# EPIP_v173.net
KiCad netlist of a schematic drawn in EAGLE
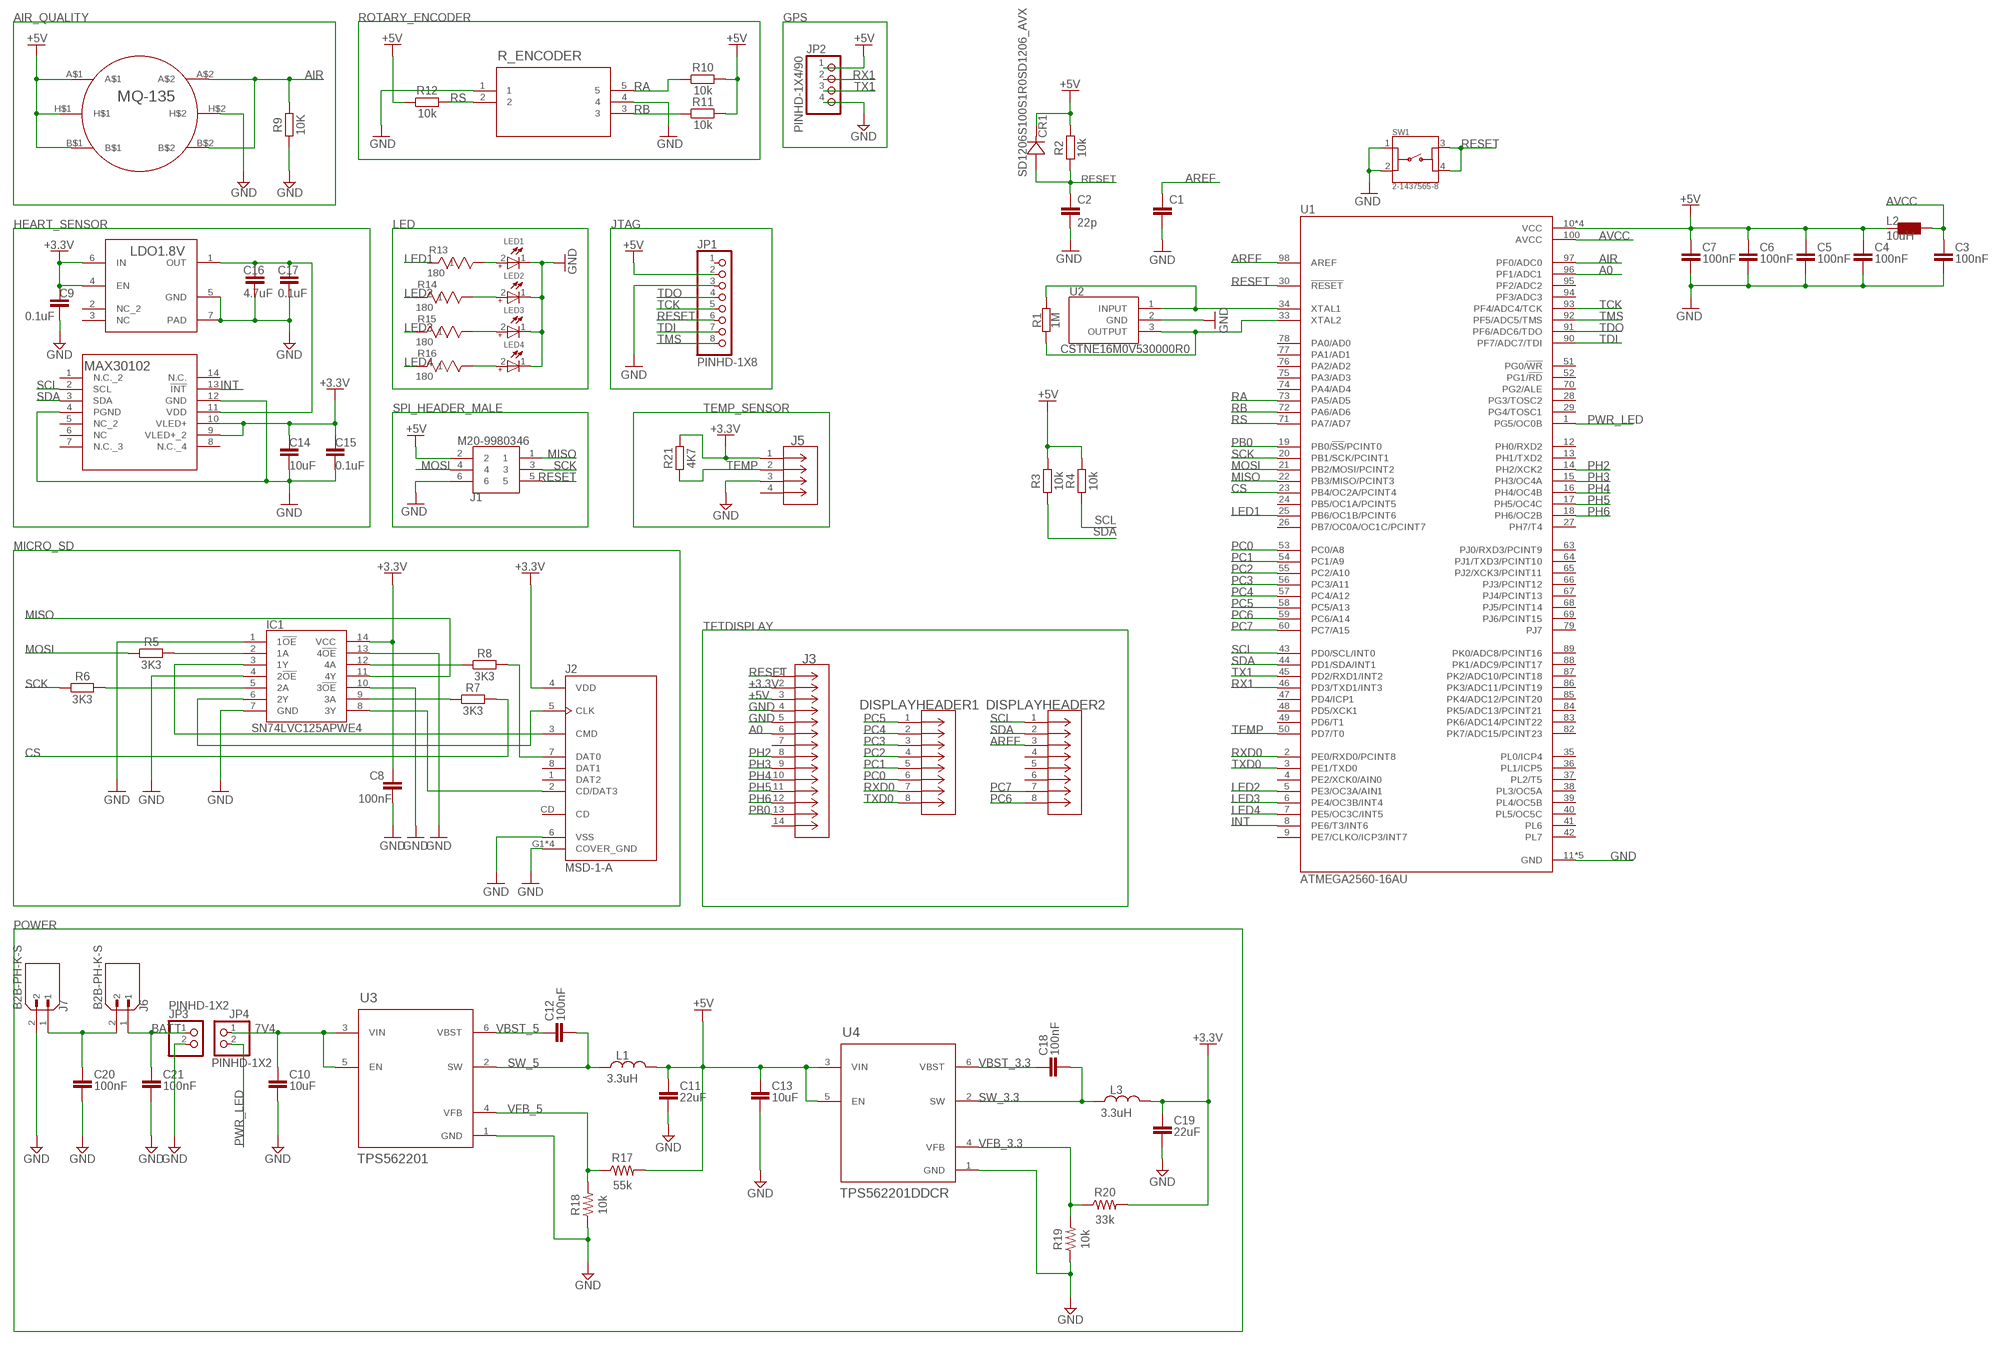
[diagram p0: schematic, sheet 1]

(export (version "E")
  (design (tool "Eeschema 10.0.6"))
  (components
    (comp (ref "C1")
      (value "100nF")
      (footprint "eagle-import:CAPC1608X85")
      (libsource (lib "eagle-import") (part "CCHIP-0603(1608-METRIC)_"))
    )
    (comp (ref "C2")
      (value "22p")
      (footprint "eagle-import:C0603-ROUND")
      (fields (field (name "PART_NUMBER") "22pF_0603"))
      (libsource (lib "eagle-import") (part "0014_22PF_0603"))
    )
    (comp (ref "C3")
      (value "100nF")
      (footprint "eagle-import:CAPC1608X85")
      (libsource (lib "eagle-import") (part "CCHIP-0603(1608-METRIC)_"))
    )
    (comp (ref "C4")
      (value "100nF")
      (footprint "eagle-import:CAPC1608X85")
      (libsource (lib "eagle-import") (part "CCHIP-0603(1608-METRIC)_"))
    )
    (comp (ref "C5")
      (value "100nF")
      (footprint "eagle-import:CAPC1608X85")
      (libsource (lib "eagle-import") (part "CCHIP-0603(1608-METRIC)_"))
    )
    (comp (ref "C6")
      (value "100nF")
      (footprint "eagle-import:CAPC1608X85")
      (libsource (lib "eagle-import") (part "CCHIP-0603(1608-METRIC)_"))
    )
    (comp (ref "C7")
      (value "100nF")
      (footprint "eagle-import:CAPC1608X85")
      (libsource (lib "eagle-import") (part "CCHIP-0603(1608-METRIC)_"))
    )
    (comp (ref "C8")
      (value "100nF")
      (footprint "eagle-import:CAPC1608X85")
      (libsource (lib "eagle-import") (part "CCHIP-0603(1608-METRIC)_"))
    )
    (comp (ref "C9")
      (value "0.1uF")
      (footprint "eagle-import:CAPC2012X110")
      (libsource (lib "eagle-import") (part "CCHIP-0805(2012-METRIC)_"))
    )
    (comp (ref "C10")
      (value "10uF")
      (footprint "eagle-import:CAPC2012X110")
      (libsource (lib "eagle-import") (part "CCHIP-0805(2012-METRIC)_"))
    )
    (comp (ref "C11")
      (value "22uF")
      (footprint "eagle-import:CAPC2012X110")
      (libsource (lib "eagle-import") (part "CCHIP-0805(2012-METRIC)_"))
    )
    (comp (ref "C12")
      (value "100nF")
      (footprint "eagle-import:CAPC1608X85")
      (libsource (lib "eagle-import") (part "CCHIP-0603(1608-METRIC)_"))
    )
    (comp (ref "C13")
      (value "10uF")
      (footprint "eagle-import:CAPC2012X110")
      (libsource (lib "eagle-import") (part "CCHIP-0805(2012-METRIC)_"))
    )
    (comp (ref "C14")
      (value "10uF")
      (footprint "eagle-import:CAPC2012X110")
      (libsource (lib "eagle-import") (part "CCHIP-0805(2012-METRIC)_"))
    )
    (comp (ref "C15")
      (value "0.1uF")
      (footprint "eagle-import:CAPC2012X110")
      (libsource (lib "eagle-import") (part "CCHIP-0805(2012-METRIC)_"))
    )
    (comp (ref "C16")
      (value "4.7uF")
      (footprint "eagle-import:CAPC1608X85")
      (libsource (lib "eagle-import") (part "CCHIP-0603(1608-METRIC)_"))
    )
    (comp (ref "C17")
      (value "0.1uF")
      (footprint "eagle-import:CAPC2012X110")
      (libsource (lib "eagle-import") (part "CCHIP-0805(2012-METRIC)_"))
    )
    (comp (ref "C18")
      (value "100nF")
      (footprint "eagle-import:CAPC1608X85")
      (libsource (lib "eagle-import") (part "CCHIP-0603(1608-METRIC)_"))
    )
    (comp (ref "C19")
      (value "22uF")
      (footprint "eagle-import:CAPC2012X110")
      (libsource (lib "eagle-import") (part "CCHIP-0805(2012-METRIC)_"))
    )
    (comp (ref "C20")
      (value "100nF")
      (footprint "eagle-import:CAPC1608X85")
      (libsource (lib "eagle-import") (part "CCHIP-0603(1608-METRIC)_"))
    )
    (comp (ref "C21")
      (value "100nF")
      (footprint "eagle-import:CAPC1608X85")
      (libsource (lib "eagle-import") (part "CCHIP-0603(1608-METRIC)_"))
    )
    (comp (ref "CR1")
      (value "SD1206S100S1R0SD1206_AVX")
      (footprint "eagle-import:SD1206_AVX")
      (fields
        (field (name "MANUFACTURER_PART_NUMBER") "SD1206S100S1R0")
        (field (name "COPYRIGHT") "Copyright (C) 2024 Ultra Librarian. All rights reserved.")
      )
      (libsource (lib "eagle-import") (part "SD1206S100S1R0SD1206_AVX"))
    )
    (comp (ref "DISPLAYHEADER1")
      (value "PPPC081LFBN-RCCONN8_LFBN-RC_SUL")
      (footprint "eagle-import:CONN8_LFBN-RC_SUL")
      (fields
        (field (name "MANUFACTURER_PART_NUMBER") "PPPC081LFBN-RC")
        (field (name "COPYRIGHT") "Copyright (C) 2024 Ultra Librarian. All rights reserved.")
      )
      (libsource (lib "eagle-import") (part "PPPC081LFBN-RCCONN8_LFBN-RC_SUL"))
    )
    (comp (ref "DISPLAYHEADER2")
      (value "PPPC081LFBN-RCCONN8_LFBN-RC_SUL")
      (footprint "eagle-import:CONN8_LFBN-RC_SUL")
      (fields
        (field (name "MANUFACTURER_PART_NUMBER") "PPPC081LFBN-RC")
        (field (name "COPYRIGHT") "Copyright (C) 2024 Ultra Librarian. All rights reserved.")
      )
      (libsource (lib "eagle-import") (part "PPPC081LFBN-RCCONN8_LFBN-RC_SUL"))
    )
    (comp (ref "IC1")
      (value "SN74LVC125APWE4")
      (footprint "eagle-import:SOP65P640X120-14N")
      (fields (field (name "MOUSER_PART_NUMBER") "595-SN74LVC125APWE4"))
      (libsource (lib "eagle-import") (part "SN74LVC125APWE4"))
    )
    (comp (ref "J1")
      (value "M20-9980346")
      (footprint "eagle-import:HDRV6W64P254_2X3_762X508X868P")
      (fields (field (name "MOUSER_PART_NUMBER") "855-M20-9980346"))
      (libsource (lib "eagle-import") (part "M20-9980346"))
    )
    (comp (ref "J2")
      (value "MSD-1-A")
      (footprint "eagle-import:CUI_MSD-1-A")
      (fields (field (name "MANUFACTURER") "CUI Devices"))
      (libsource (lib "eagle-import") (part "MSD-1-A"))
    )
    (comp (ref "J3")
      (value "PPPC141LFBN-RCCONN14_PPPN141_SUL")
      (footprint "eagle-import:CONN14_PPPN141_SUL")
      (fields
        (field (name "MANUFACTURER_PART_NUMBER") "PPPC141LFBN-RC")
        (field (name "COPYRIGHT") "Copyright (C) 2024 Ultra Librarian. All rights reserved.")
      )
      (libsource (lib "eagle-import") (part "PPPC141LFBN-RCCONN14_PPPN141_SUL"))
    )
    (comp (ref "J5")
      (value "PPTC041LFBN-RCCONN_PPTC041LFBN-RC_SUL")
      (footprint "eagle-import:CONN_PPTC041LFBN-RC_SUL")
      (fields
        (field (name "MANUFACTURER_PART_NUMBER") "PPTC041LFBN-RC")
        (field (name "COPYRIGHT") "Copyright (C) 2024 Ultra Librarian. All rights reserved.")
      )
      (libsource (lib "eagle-import") (part "PPTC041LFBN-RCCONN_PPTC041LFBN-RC_SUL"))
    )
    (comp (ref "J6")
      (value "B2B-PH-K-S")
      (footprint "eagle-import:JST_B2B-PH-K-S")
      (fields (field (name "MANUFACTURER") "JST"))
      (libsource (lib "eagle-import") (part "B2B-PH-K-S"))
    )
    (comp (ref "J7")
      (value "B2B-PH-K-S")
      (footprint "eagle-import:JST_B2B-PH-K-S")
      (fields (field (name "MANUFACTURER") "JST"))
      (libsource (lib "eagle-import") (part "B2B-PH-K-S"))
    )
    (comp (ref "JP1")
      (value "PINHD-1X8")
      (footprint "eagle-import:1X08")
      (fields (field (name "MANUFACTURER") "Generic"))
      (libsource (lib "eagle-import") (part "PINHD-1X8"))
    )
    (comp (ref "JP2")
      (value "PINHD-1X4/90")
      (footprint "eagle-import:1X04_90")
      (fields (field (name "MANUFACTURER") "Generic"))
      (libsource (lib "eagle-import") (part "PINHD-1X4/90"))
    )
    (comp (ref "JP3")
      (value "PINHD-1X2")
      (footprint "eagle-import:1X02")
      (fields (field (name "MANUFACTURER") "Generic"))
      (libsource (lib "eagle-import") (part "PINHD-1X2"))
    )
    (comp (ref "JP4")
      (value "PINHD-1X2")
      (footprint "eagle-import:1X02")
      (fields (field (name "MANUFACTURER") "Generic"))
      (libsource (lib "eagle-import") (part "PINHD-1X2"))
    )
    (comp (ref "L1")
      (value "3.3uH")
      (footprint "eagle-import:INDC2520X120N")
      (libsource (lib "eagle-import") (part "LCHIP-1008(2520-METRIC)_"))
    )
    (comp (ref "L2")
      (value "10uH")
      (footprint "eagle-import:0805")
      (fields (field (name "PART_NUMBER") "CV201210-100K"))
      (libsource (lib "eagle-import") (part "0715_CV201210-100K"))
    )
    (comp (ref "L3")
      (value "3.3uH")
      (footprint "eagle-import:INDC2520X120N")
      (libsource (lib "eagle-import") (part "LCHIP-1008(2520-METRIC)_"))
    )
    (comp (ref "LDO1.8V")
      (value "LP5910-1.8DRVRDRV0006A_NV")
      (footprint "eagle-import:DRV0006A_NV")
      (fields
        (field (name "MANUFACTURER_PART_NUMBER") "LP5910-1.8DRVR")
        (field (name "COPYRIGHT") "Copyright (C) 2024 Ultra Librarian. All rights reserved.")
      )
      (libsource (lib "eagle-import") (part "LP5910-1.8DRVRDRV0006A_NV"))
    )
    (comp (ref "LED1")
      (value "WL-TMRW_3MM_WITHOUTSTOPPER")
      (footprint "eagle-import:WL-TMRW_3MM")
      (libsource (lib "eagle-import") (part "WL-TMRW_3MM_WITHOUTSTOPPER"))
    )
    (comp (ref "LED2")
      (value "WL-TMRW_3MM_WITHOUTSTOPPER")
      (footprint "eagle-import:WL-TMRW_3MM")
      (libsource (lib "eagle-import") (part "WL-TMRW_3MM_WITHOUTSTOPPER"))
    )
    (comp (ref "LED3")
      (value "WL-TMRW_3MM_WITHOUTSTOPPER")
      (footprint "eagle-import:WL-TMRW_3MM")
      (libsource (lib "eagle-import") (part "WL-TMRW_3MM_WITHOUTSTOPPER"))
    )
    (comp (ref "LED4")
      (value "WL-TMRW_3MM_WITHOUTSTOPPER")
      (footprint "eagle-import:WL-TMRW_3MM")
      (libsource (lib "eagle-import") (part "WL-TMRW_3MM_WITHOUTSTOPPER"))
    )
    (comp (ref "MAX30102")
      (value "MAX30102EFD+T21-1048_F143A5+1_MXM-L")
      (footprint "eagle-import:21-1048_F143A5+1_MXM-L")
      (fields
        (field (name "MANUFACTURER_PART_NUMBER") "MAX30102EFD+T")
        (field (name "COPYRIGHT") "Copyright (C) 2024 Ultra Librarian. All rights reserved.")
      )
      (libsource (lib "eagle-import") (part "MAX30102EFD+T21-1048_F143A5+1_MXM-L"))
    )
    (comp (ref "R1")
      (value "1M")
      (footprint "eagle-import:RESC1608X60")
      (libsource (lib "eagle-import") (part "RCHIP-0603(1608-METRIC)_"))
    )
    (comp (ref "R2")
      (value "10k")
      (footprint "eagle-import:RESC2012X65")
      (libsource (lib "eagle-import") (part "RCHIP-0805(2012-METRIC)_"))
    )
    (comp (ref "R3")
      (value "10k")
      (footprint "eagle-import:RESC2012X65")
      (libsource (lib "eagle-import") (part "RCHIP-0805(2012-METRIC)_"))
    )
    (comp (ref "R4")
      (value "10k")
      (footprint "eagle-import:RESC2012X65")
      (libsource (lib "eagle-import") (part "RCHIP-0805(2012-METRIC)_"))
    )
    (comp (ref "R5")
      (value "3K3")
      (footprint "eagle-import:RESC2012X65")
      (libsource (lib "eagle-import") (part "RCHIP-0805(2012-METRIC)_"))
    )
    (comp (ref "R6")
      (value "3K3")
      (footprint "eagle-import:RESC2012X65")
      (libsource (lib "eagle-import") (part "RCHIP-0805(2012-METRIC)_"))
    )
    (comp (ref "R7")
      (value "3K3")
      (footprint "eagle-import:RESC2012X65")
      (libsource (lib "eagle-import") (part "RCHIP-0805(2012-METRIC)_"))
    )
    (comp (ref "R8")
      (value "3K3")
      (footprint "eagle-import:RESC2012X65")
      (libsource (lib "eagle-import") (part "RCHIP-0805(2012-METRIC)_"))
    )
    (comp (ref "R9")
      (value "10K")
      (footprint "eagle-import:RESC2012X65")
      (libsource (lib "eagle-import") (part "RESISTOR_CHIP-0805(2012-METRIC)_"))
    )
    (comp (ref "R10")
      (value "10k")
      (footprint "eagle-import:RESC2012X65")
      (libsource (lib "eagle-import") (part "RCHIP-0805(2012-METRIC)_"))
    )
    (comp (ref "R11")
      (value "10k")
      (footprint "eagle-import:RESC2012X65")
      (libsource (lib "eagle-import") (part "RCHIP-0805(2012-METRIC)_"))
    )
    (comp (ref "R12")
      (value "10k")
      (footprint "eagle-import:RESC2012X65")
      (libsource (lib "eagle-import") (part "RCHIP-0805(2012-METRIC)_"))
    )
    (comp (ref "R13")
      (value "180")
      (footprint "eagle-import:STA_RMCF0805_STP-L")
      (fields
        (field (name "MANUFACTURER_PART_NUMBER") "RMCF0805JT180R")
        (field (name "COPYRIGHT") "Copyright (C) 2024 Ultra Librarian. All rights reserved.")
      )
      (libsource (lib "eagle-import") (part "RMCF0805JT180RSTA_RMCF0805_STP-L"))
    )
    (comp (ref "R14")
      (value "180")
      (footprint "eagle-import:STA_RMCF0805_STP-L")
      (fields
        (field (name "MANUFACTURER_PART_NUMBER") "RMCF0805JT180R")
        (field (name "COPYRIGHT") "Copyright (C) 2024 Ultra Librarian. All rights reserved.")
      )
      (libsource (lib "eagle-import") (part "RMCF0805JT180RSTA_RMCF0805_STP-L"))
    )
    (comp (ref "R15")
      (value "180")
      (footprint "eagle-import:STA_RMCF0805_STP-L")
      (fields
        (field (name "MANUFACTURER_PART_NUMBER") "RMCF0805JT180R")
        (field (name "COPYRIGHT") "Copyright (C) 2024 Ultra Librarian. All rights reserved.")
      )
      (libsource (lib "eagle-import") (part "RMCF0805JT180RSTA_RMCF0805_STP-L"))
    )
    (comp (ref "R16")
      (value "180")
      (footprint "eagle-import:STA_RMCF0805_STP-L")
      (fields
        (field (name "MANUFACTURER_PART_NUMBER") "RMCF0805JT180R")
        (field (name "COPYRIGHT") "Copyright (C) 2024 Ultra Librarian. All rights reserved.")
      )
      (libsource (lib "eagle-import") (part "RMCF0805JT180RSTA_RMCF0805_STP-L"))
    )
    (comp (ref "R17")
      (value "55k")
      (footprint "eagle-import:RESC2012X65")
      (libsource (lib "eagle-import") (part "R-USCHIP-0805(2012-METRIC)_"))
    )
    (comp (ref "R18")
      (value "10k")
      (footprint "eagle-import:RESC2012X65")
      (libsource (lib "eagle-import") (part "R-USCHIP-0805(2012-METRIC)_"))
    )
    (comp (ref "R19")
      (value "10k")
      (footprint "eagle-import:RESC2012X65")
      (libsource (lib "eagle-import") (part "R-USCHIP-0805(2012-METRIC)_"))
    )
    (comp (ref "R20")
      (value "33k")
      (footprint "eagle-import:RESC2012X65")
      (libsource (lib "eagle-import") (part "R-USCHIP-0805(2012-METRIC)_"))
    )
    (comp (ref "R21")
      (value "4K7")
      (footprint "eagle-import:RESC2012X65")
      (libsource (lib "eagle-import") (part "RCHIP-0805(2012-METRIC)_"))
    )
    (comp (ref "R_ENCODER")
      (value "EN12-HS22AF30EN12")
      (footprint "eagle-import:EN12-HS_TTE")
      (fields
        (field (name "MANUFACTURER_PART_NUMBER") "EN12-HS22AF30")
        (field (name "COPYRIGHT") "Copyright (C) 2024 Ultra Librarian. All rights reserved.")
      )
      (libsource (lib "eagle-import") (part "EN12-HS22AF30EN12-HS_TTE"))
    )
    (comp (ref "SW1")
      (value "2-1437565-8")
      (footprint "eagle-import:SW_SMD_2-1437565-8_4_4.50_6.00_6.00_5.00")
      (fields (field (name "MANUFACTURER") "TE connectivity"))
      (libsource (lib "eagle-import") (part "2-1437565-8"))
    )
    (comp (ref "U$2")
      (value "MQ_135_A")
      (footprint "eagle-import:MQ-135")
      (libsource (lib "eagle-import") (part "MQ_135_A"))
    )
    (comp (ref "U1")
      (value "ATMEGA2560-16AU")
      (footprint "eagle-import:QFP50P1600X1600X120-100N")
      (fields (field (name "MANUFACTURER") "Microchip Technology"))
      (libsource (lib "eagle-import") (part "ATMEGA2560-16AU"))
    )
    (comp (ref "U2")
      (value "CSTNE16M0V530000R0")
      (footprint "eagle-import:CSTNE16M0V530000R0")
      (fields (field (name "MOUSER_PART_NUMBER") "81-CSTNE16M0V530000R"))
      (libsource (lib "eagle-import") (part "CSTNE16M0V530000R0"))
    )
    (comp (ref "U3")
      (value "TPS562201")
      (footprint "eagle-import:DDC0006A_L")
      (fields
        (field (name "MANUFACTURER_PART_NUMBER") "TPS562201DDCR")
        (field (name "COPYRIGHT") "Copyright (C) 2024 Ultra Librarian. All rights reserved.")
      )
      (libsource (lib "eagle-import") (part "TPS562201DDCRDDC0006A_L"))
    )
    (comp (ref "U4")
      (value "TPS562201DDCR")
      (footprint "eagle-import:DDC0006A_L")
      (fields (field (name "COPYRIGHT") "Copyright (C) 2024 Ultra Librarian. All rights reserved."))
      (libsource (lib "eagle-import") (part "TPS562201DDCRDDC0006A_L"))
    )
  )
  (nets
    (net (code "1") (name "+3.3V") (class "Default")
      (node (ref "C14") (pin "1") (pinfunction "1_1") (pintype "passive"))
      (node (ref "C15") (pin "1") (pinfunction "1_1") (pintype "passive"))
      (node (ref "C19") (pin "1") (pinfunction "1_1") (pintype "passive"))
      (node (ref "C8") (pin "1") (pinfunction "1_1") (pintype "passive"))
      (node (ref "C9") (pin "1") (pinfunction "1_1") (pintype "passive"))
      (node (ref "IC1") (pin "14") (pinfunction "VCC_14") (pintype "bidirectional"))
      (node (ref "J2") (pin "4") (pinfunction "VDD_4") (pintype "power_in"))
      (node (ref "J3") (pin "2") (pinfunction "2_2") (pintype "passive"))
      (node (ref "J5") (pin "1") (pinfunction "1_1") (pintype "passive"))
      (node (ref "L3") (pin "2") (pinfunction "2_2") (pintype "passive"))
      (node (ref "LDO1.8V") (pin "4") (pinfunction "EN_4") (pintype "input"))
      (node (ref "LDO1.8V") (pin "6") (pinfunction "IN_6") (pintype "power_in"))
      (node (ref "MAX30102") (pin "10") (pinfunction "VLED+_10") (pintype "passive"))
      (node (ref "MAX30102") (pin "9") (pinfunction "VLED+_2_9") (pintype "passive"))
      (node (ref "R20") (pin "2") (pinfunction "2_2") (pintype "passive"))
      (node (ref "R21") (pin "2") (pinfunction "2_2") (pintype "passive"))
    )
    (net (code "2") (name "+5V") (class "Default")
      (node (ref "C11") (pin "1") (pinfunction "1_1") (pintype "passive"))
      (node (ref "C13") (pin "1") (pinfunction "1_1") (pintype "passive"))
      (node (ref "C4") (pin "1") (pinfunction "1_1") (pintype "passive"))
      (node (ref "C5") (pin "1") (pinfunction "1_1") (pintype "passive"))
      (node (ref "C6") (pin "1") (pinfunction "1_1") (pintype "passive"))
      (node (ref "C7") (pin "1") (pinfunction "1_1") (pintype "passive"))
      (node (ref "CR1") (pin "1") (pinfunction "1_1") (pintype "passive"))
      (node (ref "J1") (pin "2") (pinfunction "2_2") (pintype "bidirectional"))
      (node (ref "J3") (pin "3") (pinfunction "3_3") (pintype "passive"))
      (node (ref "JP1") (pin "2") (pinfunction "2_2") (pintype "passive"))
      (node (ref "JP2") (pin "1") (pinfunction "1_1") (pintype "passive"))
      (node (ref "L1") (pin "2") (pinfunction "2_2") (pintype "passive"))
      (node (ref "L2") (pin "2") (pinfunction "2_2") (pintype "passive"))
      (node (ref "R10") (pin "2") (pinfunction "2_2") (pintype "passive"))
      (node (ref "R11") (pin "2") (pinfunction "2_2") (pintype "passive"))
      (node (ref "R12") (pin "1") (pinfunction "1_1") (pintype "passive"))
      (node (ref "R17") (pin "2") (pinfunction "2_2") (pintype "passive"))
      (node (ref "R2") (pin "2") (pinfunction "2_2") (pintype "passive"))
      (node (ref "R3") (pin "2") (pinfunction "2_2") (pintype "passive"))
      (node (ref "R4") (pin "2") (pinfunction "2_2") (pintype "passive"))
      (node (ref "U$2") (pin "A$1") (pinfunction "A$1_A$1") (pintype "bidirectional"))
      (node (ref "U$2") (pin "B$1") (pinfunction "B$1_B$1") (pintype "bidirectional"))
      (node (ref "U$2") (pin "H$1") (pinfunction "H$1_H$1") (pintype "bidirectional"))
      (node (ref "U1") (pin "10") (pinfunction "VCC_10") (pintype "power_in"))
      (node (ref "U1") (pin "31") (pinfunction "VCC_31") (pintype "power_in"))
      (node (ref "U1") (pin "61") (pinfunction "VCC_61") (pintype "power_in"))
      (node (ref "U1") (pin "80") (pinfunction "VCC_80") (pintype "power_in"))
      (node (ref "U4") (pin "3") (pinfunction "VIN_3") (pintype "power_in"))
      (node (ref "U4") (pin "5") (pinfunction "EN_5") (pintype "input"))
    )
    (net (code "3") (name "/7V4") (class "Default")
      (node (ref "C10") (pin "1") (pinfunction "1_1") (pintype "passive"))
      (node (ref "JP4") (pin "1") (pinfunction "1_1") (pintype "passive"))
      (node (ref "U3") (pin "3") (pinfunction "VIN_3") (pintype "power_in"))
      (node (ref "U3") (pin "5") (pinfunction "EN_5") (pintype "input"))
    )
    (net (code "4") (name "/A0") (class "Default")
      (node (ref "J3") (pin "6") (pinfunction "6_6") (pintype "passive"))
      (node (ref "U1") (pin "96") (pinfunction "PF1/ADC1_96") (pintype "bidirectional"))
    )
    (net (code "5") (name "/AIR") (class "Default")
      (node (ref "R9") (pin "2") (pinfunction "2_2") (pintype "passive"))
      (node (ref "U$2") (pin "A$2") (pinfunction "A$2_A$2") (pintype "bidirectional"))
      (node (ref "U$2") (pin "B$2") (pinfunction "B$2_B$2") (pintype "bidirectional"))
      (node (ref "U1") (pin "97") (pinfunction "PF0/ADC0_97") (pintype "bidirectional"))
    )
    (net (code "7") (name "/AREF") (class "Default")
      (node (ref "C1") (pin "1") (pinfunction "1_1") (pintype "passive"))
      (node (ref "DISPLAYHEADER2") (pin "3") (pinfunction "3_3") (pintype "passive"))
      (node (ref "U1") (pin "98") (pinfunction "AREF_98") (pintype "input"))
    )
    (net (code "8") (name "/AVCC") (class "Default")
      (node (ref "C3") (pin "1") (pinfunction "1_1") (pintype "passive"))
      (node (ref "L2") (pin "1") (pinfunction "1_1") (pintype "passive"))
      (node (ref "U1") (pin "100") (pinfunction "AVCC_100") (pintype "power_in"))
    )
    (net (code "9") (name "/BATT") (class "Default")
      (node (ref "C21") (pin "1") (pinfunction "1_1") (pintype "passive"))
      (node (ref "J6") (pin "1") (pinfunction "1_1") (pintype "passive"))
      (node (ref "JP3") (pin "1") (pinfunction "1_1") (pintype "passive"))
    )
    (net (code "10") (name "/CS") (class "Default")
      (node (ref "R7") (pin "2") (pinfunction "2_2") (pintype "passive"))
      (node (ref "U1") (pin "23") (pinfunction "PB4/OC2A/PCINT4_23") (pintype "bidirectional"))
    )
    (net (code "13") (name "/INT") (class "Default")
      (node (ref "MAX30102") (pin "13") (pinfunction "~{INT}_13") (pintype "passive"))
      (node (ref "U1") (pin "8") (pinfunction "PE6/T3/INT6_8") (pintype "bidirectional"))
    )
    (net (code "16") (name "/LED1") (class "Default")
      (node (ref "R13") (pin "1") (pinfunction "1_1") (pintype "passive"))
      (node (ref "U1") (pin "25") (pinfunction "PB6/OC1B/PCINT6_25") (pintype "bidirectional"))
    )
    (net (code "17") (name "/LED2") (class "Default")
      (node (ref "R14") (pin "1") (pinfunction "1_1") (pintype "passive"))
      (node (ref "U1") (pin "5") (pinfunction "PE3/OC3A/AIN1_5") (pintype "bidirectional"))
    )
    (net (code "18") (name "/LED3") (class "Default")
      (node (ref "R15") (pin "1") (pinfunction "1_1") (pintype "passive"))
      (node (ref "U1") (pin "6") (pinfunction "PE4/OC3B/INT4_6") (pintype "bidirectional"))
    )
    (net (code "19") (name "/LED4") (class "Default")
      (node (ref "R16") (pin "1") (pinfunction "1_1") (pintype "passive"))
      (node (ref "U1") (pin "7") (pinfunction "PE5/OC3C/INT5_7") (pintype "bidirectional"))
    )
    (net (code "21") (name "/MISO") (class "Default")
      (node (ref "IC1") (pin "11") (pinfunction "4Y_11") (pintype "bidirectional"))
      (node (ref "J1") (pin "1") (pinfunction "1_1") (pintype "bidirectional"))
      (node (ref "U1") (pin "22") (pinfunction "PB3/MISO/PCINT3_22") (pintype "bidirectional"))
    )
    (net (code "22") (name "/MOSI") (class "Default")
      (node (ref "J1") (pin "4") (pinfunction "4_4") (pintype "bidirectional"))
      (node (ref "R5") (pin "1") (pinfunction "1_1") (pintype "passive"))
      (node (ref "U1") (pin "21") (pinfunction "PB2/MOSI/PCINT2_21") (pintype "bidirectional"))
    )
    (net (code "23") (name "/PB0") (class "Default")
      (node (ref "J3") (pin "13") (pinfunction "13_13") (pintype "passive"))
      (node (ref "U1") (pin "19") (pinfunction "PB0/~{SS}/PCINT0_19") (pintype "bidirectional"))
    )
    (net (code "24") (name "/PC0") (class "Default")
      (node (ref "DISPLAYHEADER1") (pin "6") (pinfunction "6_6") (pintype "passive"))
      (node (ref "U1") (pin "53") (pinfunction "PC0/A8_53") (pintype "bidirectional"))
    )
    (net (code "25") (name "/PC1") (class "Default")
      (node (ref "DISPLAYHEADER1") (pin "5") (pinfunction "5_5") (pintype "passive"))
      (node (ref "U1") (pin "54") (pinfunction "PC1/A9_54") (pintype "bidirectional"))
    )
    (net (code "26") (name "/PC2") (class "Default")
      (node (ref "DISPLAYHEADER1") (pin "4") (pinfunction "4_4") (pintype "passive"))
      (node (ref "U1") (pin "55") (pinfunction "PC2/A10_55") (pintype "bidirectional"))
    )
    (net (code "27") (name "/PC3") (class "Default")
      (node (ref "DISPLAYHEADER1") (pin "3") (pinfunction "3_3") (pintype "passive"))
      (node (ref "U1") (pin "56") (pinfunction "PC3/A11_56") (pintype "bidirectional"))
    )
    (net (code "28") (name "/PC4") (class "Default")
      (node (ref "DISPLAYHEADER1") (pin "2") (pinfunction "2_2") (pintype "passive"))
      (node (ref "U1") (pin "57") (pinfunction "PC4/A12_57") (pintype "bidirectional"))
    )
    (net (code "29") (name "/PC5") (class "Default")
      (node (ref "DISPLAYHEADER1") (pin "1") (pinfunction "1_1") (pintype "passive"))
      (node (ref "U1") (pin "58") (pinfunction "PC5/A13_58") (pintype "bidirectional"))
    )
    (net (code "30") (name "/PC6") (class "Default")
      (node (ref "DISPLAYHEADER2") (pin "8") (pinfunction "8_8") (pintype "passive"))
      (node (ref "U1") (pin "59") (pinfunction "PC6/A14_59") (pintype "bidirectional"))
    )
    (net (code "31") (name "/PC7") (class "Default")
      (node (ref "DISPLAYHEADER2") (pin "7") (pinfunction "7_7") (pintype "passive"))
      (node (ref "U1") (pin "60") (pinfunction "PC7/A15_60") (pintype "bidirectional"))
    )
    (net (code "32") (name "/PH2") (class "Default")
      (node (ref "J3") (pin "8") (pinfunction "8_8") (pintype "passive"))
      (node (ref "U1") (pin "14") (pinfunction "PH2/XCK2_14") (pintype "bidirectional"))
    )
    (net (code "33") (name "/PH3") (class "Default")
      (node (ref "J3") (pin "9") (pinfunction "9_9") (pintype "passive"))
      (node (ref "U1") (pin "15") (pinfunction "PH3/OC4A_15") (pintype "bidirectional"))
    )
    (net (code "34") (name "/PH4") (class "Default")
      (node (ref "J3") (pin "10") (pinfunction "10_10") (pintype "passive"))
      (node (ref "U1") (pin "16") (pinfunction "PH4/OC4B_16") (pintype "bidirectional"))
    )
    (net (code "35") (name "/PH5") (class "Default")
      (node (ref "J3") (pin "11") (pinfunction "11_11") (pintype "passive"))
      (node (ref "U1") (pin "17") (pinfunction "PH5/OC4C_17") (pintype "bidirectional"))
    )
    (net (code "36") (name "/PH6") (class "Default")
      (node (ref "J3") (pin "12") (pinfunction "12_12") (pintype "passive"))
      (node (ref "U1") (pin "18") (pinfunction "PH6/OC2B_18") (pintype "bidirectional"))
    )
    (net (code "38") (name "/PWR_LED") (class "Default")
      (node (ref "JP4") (pin "2") (pinfunction "2_2") (pintype "passive"))
      (node (ref "U1") (pin "1") (pinfunction "PG5/OC0B_1") (pintype "bidirectional"))
    )
    (net (code "39") (name "/RA") (class "Default")
      (node (ref "R10") (pin "1") (pinfunction "1_1") (pintype "passive"))
      (node (ref "R_ENCODER") (pin "5") (pinfunction "5_5") (pintype "passive"))
      (node (ref "U1") (pin "73") (pinfunction "PA5/AD5_73") (pintype "bidirectional"))
    )
    (net (code "40") (name "/RB") (class "Default")
      (node (ref "R11") (pin "1") (pinfunction "1_1") (pintype "passive"))
      (node (ref "R_ENCODER") (pin "3") (pinfunction "3_3") (pintype "passive"))
      (node (ref "U1") (pin "72") (pinfunction "PA6/AD6_72") (pintype "bidirectional"))
    )
    (net (code "41") (name "/RESET") (class "Default")
      (node (ref "C2") (pin "1") (pinfunction "1_1") (pintype "passive"))
      (node (ref "CR1") (pin "2") (pinfunction "2_2") (pintype "passive"))
      (node (ref "J1") (pin "5") (pinfunction "5_5") (pintype "bidirectional"))
      (node (ref "J3") (pin "1") (pinfunction "1_1") (pintype "passive"))
      (node (ref "JP1") (pin "6") (pinfunction "6_6") (pintype "passive"))
      (node (ref "R2") (pin "1") (pinfunction "1_1") (pintype "passive"))
      (node (ref "SW1") (pin "3") (pinfunction "3_3") (pintype "passive"))
      (node (ref "SW1") (pin "4") (pinfunction "4_4") (pintype "passive"))
      (node (ref "U1") (pin "30") (pinfunction "~{RESET}_30") (pintype "input"))
    )
    (net (code "43") (name "/RS") (class "Default")
      (node (ref "R12") (pin "2") (pinfunction "2_2") (pintype "passive"))
      (node (ref "R_ENCODER") (pin "2") (pinfunction "2_2") (pintype "passive"))
      (node (ref "U1") (pin "71") (pinfunction "PA7/AD7_71") (pintype "bidirectional"))
    )
    (net (code "44") (name "/RX1") (class "Default")
      (node (ref "JP2") (pin "2") (pinfunction "2_2") (pintype "passive"))
      (node (ref "U1") (pin "46") (pinfunction "PD3/TXD1/INT3_46") (pintype "bidirectional"))
    )
    (net (code "45") (name "/RXD0") (class "Default")
      (node (ref "DISPLAYHEADER1") (pin "7") (pinfunction "7_7") (pintype "passive"))
      (node (ref "U1") (pin "2") (pinfunction "PE0/RXD0/PCINT8_2") (pintype "bidirectional"))
    )
    (net (code "46") (name "/SCK") (class "Default")
      (node (ref "J1") (pin "3") (pinfunction "3_3") (pintype "bidirectional"))
      (node (ref "R6") (pin "1") (pinfunction "1_1") (pintype "passive"))
      (node (ref "U1") (pin "20") (pinfunction "PB1/SCK/PCINT1_20") (pintype "bidirectional"))
    )
    (net (code "47") (name "/SCL") (class "Default")
      (node (ref "DISPLAYHEADER2") (pin "1") (pinfunction "1_1") (pintype "passive"))
      (node (ref "MAX30102") (pin "2") (pinfunction "SCL_2") (pintype "passive"))
      (node (ref "R4") (pin "1") (pinfunction "1_1") (pintype "passive"))
      (node (ref "U1") (pin "43") (pinfunction "PD0/SCL/INT0_43") (pintype "bidirectional"))
    )
    (net (code "48") (name "/SDA") (class "Default")
      (node (ref "DISPLAYHEADER2") (pin "2") (pinfunction "2_2") (pintype "passive"))
      (node (ref "MAX30102") (pin "3") (pinfunction "SDA_3") (pintype "passive"))
      (node (ref "R3") (pin "1") (pinfunction "1_1") (pintype "passive"))
      (node (ref "U1") (pin "44") (pinfunction "PD1/SDA/INT1_44") (pintype "bidirectional"))
    )
    (net (code "50") (name "/SW_3.3") (class "Default")
      (node (ref "C18") (pin "2") (pinfunction "2_2") (pintype "passive"))
      (node (ref "L3") (pin "1") (pinfunction "1_1") (pintype "passive"))
      (node (ref "U4") (pin "2") (pinfunction "SW_2") (pintype "power_in"))
    )
    (net (code "51") (name "/SW_5") (class "Default")
      (node (ref "C12") (pin "2") (pinfunction "2_2") (pintype "passive"))
      (node (ref "L1") (pin "1") (pinfunction "1_1") (pintype "passive"))
      (node (ref "U3") (pin "2") (pinfunction "SW_2") (pintype "power_in"))
    )
    (net (code "52") (name "/TCK") (class "Default")
      (node (ref "JP1") (pin "5") (pinfunction "5_5") (pintype "passive"))
      (node (ref "U1") (pin "93") (pinfunction "PF4/ADC4/TCK_93") (pintype "bidirectional"))
    )
    (net (code "53") (name "/TDI") (class "Default")
      (node (ref "JP1") (pin "7") (pinfunction "7_7") (pintype "passive"))
      (node (ref "U1") (pin "90") (pinfunction "PF7/ADC7/TDI_90") (pintype "bidirectional"))
    )
    (net (code "54") (name "/TDO") (class "Default")
      (node (ref "JP1") (pin "4") (pinfunction "4_4") (pintype "passive"))
      (node (ref "U1") (pin "91") (pinfunction "PF6/ADC6/TDO_91") (pintype "bidirectional"))
    )
    (net (code "55") (name "/TEMP") (class "Default")
      (node (ref "J5") (pin "2") (pinfunction "2_2") (pintype "passive"))
      (node (ref "R21") (pin "1") (pinfunction "1_1") (pintype "passive"))
      (node (ref "U1") (pin "50") (pinfunction "PD7/T0_50") (pintype "bidirectional"))
    )
    (net (code "58") (name "/TMS") (class "Default")
      (node (ref "JP1") (pin "8") (pinfunction "8_8") (pintype "passive"))
      (node (ref "U1") (pin "92") (pinfunction "PF5/ADC5/TMS_92") (pintype "bidirectional"))
    )
    (net (code "59") (name "/TX1") (class "Default")
      (node (ref "JP2") (pin "3") (pinfunction "3_3") (pintype "passive"))
      (node (ref "U1") (pin "45") (pinfunction "PD2/RXD1/INT2_45") (pintype "bidirectional"))
    )
    (net (code "60") (name "/TXD0") (class "Default")
      (node (ref "DISPLAYHEADER1") (pin "8") (pinfunction "8_8") (pintype "passive"))
      (node (ref "U1") (pin "3") (pinfunction "PE1/TXD0_3") (pintype "bidirectional"))
    )
    (net (code "61") (name "/VBST_3.3") (class "Default")
      (node (ref "C18") (pin "1") (pinfunction "1_1") (pintype "passive"))
      (node (ref "U4") (pin "6") (pinfunction "VBST_6") (pintype "power_in"))
    )
    (net (code "62") (name "/VBST_5") (class "Default")
      (node (ref "C12") (pin "1") (pinfunction "1_1") (pintype "passive"))
      (node (ref "U3") (pin "6") (pinfunction "VBST_6") (pintype "power_in"))
    )
    (net (code "63") (name "/VFB_3.3") (class "Default")
      (node (ref "R19") (pin "2") (pinfunction "2_2") (pintype "passive"))
      (node (ref "R20") (pin "1") (pinfunction "1_1") (pintype "passive"))
      (node (ref "U4") (pin "4") (pinfunction "VFB_4") (pintype "input"))
    )
    (net (code "64") (name "/VFB_5") (class "Default")
      (node (ref "R17") (pin "1") (pinfunction "1_1") (pintype "passive"))
      (node (ref "R18") (pin "2") (pinfunction "2_2") (pintype "passive"))
      (node (ref "U3") (pin "4") (pinfunction "VFB_4") (pintype "input"))
    )
    (net (code "65") (name "GND") (class "Default")
      (node (ref "C1") (pin "2") (pinfunction "2_2") (pintype "passive"))
      (node (ref "C10") (pin "2") (pinfunction "2_2") (pintype "passive"))
      (node (ref "C11") (pin "2") (pinfunction "2_2") (pintype "passive"))
      (node (ref "C13") (pin "2") (pinfunction "2_2") (pintype "passive"))
      (node (ref "C14") (pin "2") (pinfunction "2_2") (pintype "passive"))
      (node (ref "C15") (pin "2") (pinfunction "2_2") (pintype "passive"))
      (node (ref "C16") (pin "2") (pinfunction "2_2") (pintype "passive"))
      (node (ref "C17") (pin "2") (pinfunction "2_2") (pintype "passive"))
      (node (ref "C19") (pin "2") (pinfunction "2_2") (pintype "passive"))
      (node (ref "C2") (pin "2") (pinfunction "2_2") (pintype "passive"))
      (node (ref "C20") (pin "2") (pinfunction "2_2") (pintype "passive"))
      (node (ref "C21") (pin "2") (pinfunction "2_2") (pintype "passive"))
      (node (ref "C3") (pin "2") (pinfunction "2_2") (pintype "passive"))
      (node (ref "C4") (pin "2") (pinfunction "2_2") (pintype "passive"))
      (node (ref "C5") (pin "2") (pinfunction "2_2") (pintype "passive"))
      (node (ref "C6") (pin "2") (pinfunction "2_2") (pintype "passive"))
      (node (ref "C7") (pin "2") (pinfunction "2_2") (pintype "passive"))
      (node (ref "C8") (pin "2") (pinfunction "2_2") (pintype "passive"))
      (node (ref "C9") (pin "2") (pinfunction "2_2") (pintype "passive"))
      (node (ref "IC1") (pin "1") (pinfunction "1~{OE}_1") (pintype "bidirectional"))
      (node (ref "IC1") (pin "10") (pinfunction "3~{OE}_10") (pintype "bidirectional"))
      (node (ref "IC1") (pin "13") (pinfunction "4~{OE}_13") (pintype "bidirectional"))
      (node (ref "IC1") (pin "4") (pinfunction "2~{OE}_4") (pintype "bidirectional"))
      (node (ref "IC1") (pin "7") (pinfunction "GND_7") (pintype "bidirectional"))
      (node (ref "J1") (pin "6") (pinfunction "6_6") (pintype "bidirectional"))
      (node (ref "J2") (pin "6") (pinfunction "VSS_6") (pintype "power_in"))
      (node (ref "J2") (pin "G1") (pinfunction "COVER_GND_G1") (pintype "power_in"))
      (node (ref "J2") (pin "G2") (pinfunction "COVER_GND_G2") (pintype "power_in"))
      (node (ref "J2") (pin "G3") (pinfunction "COVER_GND_G3") (pintype "power_in"))
      (node (ref "J2") (pin "G4") (pinfunction "COVER_GND_G4") (pintype "power_in"))
      (node (ref "J3") (pin "4") (pinfunction "4_4") (pintype "passive"))
      (node (ref "J3") (pin "5") (pinfunction "5_5") (pintype "passive"))
      (node (ref "J5") (pin "3") (pinfunction "3_3") (pintype "passive"))
      (node (ref "J7") (pin "2") (pinfunction "2_2") (pintype "passive"))
      (node (ref "JP1") (pin "3") (pinfunction "3_3") (pintype "passive"))
      (node (ref "JP2") (pin "4") (pinfunction "4_4") (pintype "passive"))
      (node (ref "JP3") (pin "2") (pinfunction "2_2") (pintype "passive"))
      (node (ref "LDO1.8V") (pin "5") (pinfunction "GND_5") (pintype "passive"))
      (node (ref "LDO1.8V") (pin "7") (pinfunction "PAD_7") (pintype "passive"))
      (node (ref "LED1") (pin "1") (pinfunction "-_1") (pintype "passive"))
      (node (ref "LED2") (pin "1") (pinfunction "-_1") (pintype "passive"))
      (node (ref "LED3") (pin "1") (pinfunction "-_1") (pintype "passive"))
      (node (ref "LED4") (pin "1") (pinfunction "-_1") (pintype "passive"))
      (node (ref "MAX30102") (pin "12") (pinfunction "GND_12") (pintype "passive"))
      (node (ref "MAX30102") (pin "4") (pinfunction "PGND_4") (pintype "passive"))
      (node (ref "R18") (pin "1") (pinfunction "1_1") (pintype "passive"))
      (node (ref "R19") (pin "1") (pinfunction "1_1") (pintype "passive"))
      (node (ref "R9") (pin "1") (pinfunction "1_1") (pintype "passive"))
      (node (ref "R_ENCODER") (pin "1") (pinfunction "1_1") (pintype "passive"))
      (node (ref "R_ENCODER") (pin "4") (pinfunction "4_4") (pintype "passive"))
      (node (ref "SW1") (pin "1") (pinfunction "1_1") (pintype "passive"))
      (node (ref "SW1") (pin "2") (pinfunction "2_2") (pintype "passive"))
      (node (ref "U$2") (pin "H$2") (pinfunction "H$2_H$2") (pintype "bidirectional"))
      (node (ref "U1") (pin "11") (pinfunction "GND_11") (pintype "power_in"))
      (node (ref "U1") (pin "32") (pinfunction "GND_32") (pintype "power_in"))
      (node (ref "U1") (pin "62") (pinfunction "GND_62") (pintype "power_in"))
      (node (ref "U1") (pin "81") (pinfunction "GND_81") (pintype "power_in"))
      (node (ref "U1") (pin "99") (pinfunction "GND_99") (pintype "power_in"))
      (node (ref "U2") (pin "2") (pinfunction "GND_2") (pintype "bidirectional"))
      (node (ref "U3") (pin "1") (pinfunction "GND_1") (pintype "power_in"))
      (node (ref "U4") (pin "1") (pinfunction "GND_1") (pintype "power_in"))
    )
    (net (code "66") (name "Net-(C20-Pad1)") (class "Default")
      (node (ref "C20") (pin "1") (pinfunction "1_1") (pintype "passive"))
      (node (ref "J6") (pin "2") (pinfunction "2_2") (pintype "passive"))
      (node (ref "J7") (pin "1") (pinfunction "1_1") (pintype "passive"))
    )
    (net (code "67") (name "Net-(IC1-1A)") (class "Default")
      (node (ref "IC1") (pin "2") (pinfunction "1A_2") (pintype "bidirectional"))
      (node (ref "R5") (pin "2") (pinfunction "2_2") (pintype "passive"))
    )
    (net (code "68") (name "Net-(IC1-1Y)") (class "Default")
      (node (ref "IC1") (pin "3") (pinfunction "1Y_3") (pintype "bidirectional"))
      (node (ref "J2") (pin "3") (pinfunction "CMD_3") (pintype "bidirectional"))
    )
    (net (code "69") (name "Net-(IC1-2A)") (class "Default")
      (node (ref "IC1") (pin "5") (pinfunction "2A_5") (pintype "bidirectional"))
      (node (ref "R6") (pin "2") (pinfunction "2_2") (pintype "passive"))
    )
    (net (code "70") (name "Net-(IC1-2Y)") (class "Default")
      (node (ref "IC1") (pin "6") (pinfunction "2Y_6") (pintype "bidirectional"))
      (node (ref "J2") (pin "5") (pinfunction "CLK_5") (pintype "input"))
    )
    (net (code "71") (name "Net-(IC1-3A)") (class "Default")
      (node (ref "IC1") (pin "9") (pinfunction "3A_9") (pintype "bidirectional"))
      (node (ref "R7") (pin "1") (pinfunction "1_1") (pintype "passive"))
    )
    (net (code "72") (name "Net-(IC1-3Y)") (class "Default")
      (node (ref "IC1") (pin "8") (pinfunction "3Y_8") (pintype "bidirectional"))
      (node (ref "J2") (pin "2") (pinfunction "CD/DAT3_2") (pintype "bidirectional"))
    )
    (net (code "73") (name "Net-(IC1-4A)") (class "Default")
      (node (ref "IC1") (pin "12") (pinfunction "4A_12") (pintype "bidirectional"))
      (node (ref "R8") (pin "1") (pinfunction "1_1") (pintype "passive"))
    )
    (net (code "74") (name "Net-(J2-DAT0)") (class "Default")
      (node (ref "J2") (pin "7") (pinfunction "DAT0_7") (pintype "bidirectional"))
      (node (ref "R8") (pin "2") (pinfunction "2_2") (pintype "passive"))
    )
    (net (code "75") (name "Net-(LDO1.8V-OUT)") (class "Default")
      (node (ref "C16") (pin "1") (pinfunction "1_1") (pintype "passive"))
      (node (ref "C17") (pin "1") (pinfunction "1_1") (pintype "passive"))
      (node (ref "LDO1.8V") (pin "1") (pinfunction "OUT_1") (pintype "power_in"))
      (node (ref "MAX30102") (pin "11") (pinfunction "VDD_11") (pintype "power_in"))
    )
    (net (code "76") (name "Net-(LED1-+)") (class "Default")
      (node (ref "LED1") (pin "2") (pinfunction "+_2") (pintype "passive"))
      (node (ref "R13") (pin "2") (pinfunction "2_2") (pintype "passive"))
    )
    (net (code "77") (name "Net-(LED2-+)") (class "Default")
      (node (ref "LED2") (pin "2") (pinfunction "+_2") (pintype "passive"))
      (node (ref "R14") (pin "2") (pinfunction "2_2") (pintype "passive"))
    )
    (net (code "78") (name "Net-(LED3-+)") (class "Default")
      (node (ref "LED3") (pin "2") (pinfunction "+_2") (pintype "passive"))
      (node (ref "R15") (pin "2") (pinfunction "2_2") (pintype "passive"))
    )
    (net (code "79") (name "Net-(LED4-+)") (class "Default")
      (node (ref "LED4") (pin "2") (pinfunction "+_2") (pintype "passive"))
      (node (ref "R16") (pin "2") (pinfunction "2_2") (pintype "passive"))
    )
    (net (code "80") (name "Net-(U1-XTAL1)") (class "Default")
      (node (ref "R1") (pin "2") (pinfunction "2_2") (pintype "passive"))
      (node (ref "U1") (pin "34") (pinfunction "XTAL1_34") (pintype "input"))
      (node (ref "U2") (pin "1") (pinfunction "INPUT_1") (pintype "bidirectional"))
    )
    (net (code "81") (name "Net-(U1-XTAL2)") (class "Default")
      (node (ref "R1") (pin "1") (pinfunction "1_1") (pintype "passive"))
      (node (ref "U1") (pin "33") (pinfunction "XTAL2_33") (pintype "output"))
      (node (ref "U2") (pin "3") (pinfunction "OUTPUT_3") (pintype "bidirectional"))
    )
    (net (code "82") (name "unconnected-(DISPLAYHEADER2-Pad4)") (class "Default")
      (node (ref "DISPLAYHEADER2") (pin "4") (pinfunction "4_4") (pintype "passive"))
    )
    (net (code "83") (name "unconnected-(DISPLAYHEADER2-Pad5)") (class "Default")
      (node (ref "DISPLAYHEADER2") (pin "5") (pinfunction "5_5") (pintype "passive"))
    )
    (net (code "84") (name "unconnected-(DISPLAYHEADER2-Pad6)") (class "Default")
      (node (ref "DISPLAYHEADER2") (pin "6") (pinfunction "6_6") (pintype "passive"))
    )
    (net (code "85") (name "unconnected-(J2-DAT1-Pad8)") (class "Default")
      (node (ref "J2") (pin "8") (pinfunction "DAT1_8") (pintype "bidirectional"))
    )
    (net (code "86") (name "unconnected-(J2-DAT2-Pad1)") (class "Default")
      (node (ref "J2") (pin "1") (pinfunction "DAT2_1") (pintype "bidirectional"))
    )
    (net (code "87") (name "unconnected-(J2-PadCD)") (class "Default")
      (node (ref "J2") (pin "CD") (pinfunction "CD_CD") (pintype "passive"))
    )
    (net (code "88") (name "unconnected-(J3-Pad7)") (class "Default")
      (node (ref "J3") (pin "7") (pinfunction "7_7") (pintype "passive"))
    )
    (net (code "89") (name "unconnected-(J3-Pad14)") (class "Default")
      (node (ref "J3") (pin "14") (pinfunction "14_14") (pintype "passive"))
    )
    (net (code "90") (name "unconnected-(J5-Pad4)") (class "Default")
      (node (ref "J5") (pin "4") (pinfunction "4_4") (pintype "passive"))
    )
    (net (code "91") (name "unconnected-(JP1-Pad1)") (class "Default")
      (node (ref "JP1") (pin "1") (pinfunction "1_1") (pintype "passive"))
    )
    (net (code "92") (name "unconnected-(LDO1.8V-NC-Pad3)") (class "Default")
      (node (ref "LDO1.8V") (pin "3") (pinfunction "NC_3") (pintype "passive"))
    )
    (net (code "93") (name "unconnected-(LDO1.8V-NC_2-Pad2)") (class "Default")
      (node (ref "LDO1.8V") (pin "2") (pinfunction "NC_2_2") (pintype "passive"))
    )
    (net (code "94") (name "unconnected-(MAX30102-N.C.-Pad14)") (class "Default")
      (node (ref "MAX30102") (pin "14") (pinfunction "N.C._14") (pintype "no_connect"))
    )
    (net (code "95") (name "unconnected-(MAX30102-N.C._2-Pad1)") (class "Default")
      (node (ref "MAX30102") (pin "1") (pinfunction "N.C._2_1") (pintype "no_connect"))
    )
    (net (code "96") (name "unconnected-(MAX30102-N.C._3-Pad7)") (class "Default")
      (node (ref "MAX30102") (pin "7") (pinfunction "N.C._3_7") (pintype "no_connect"))
    )
    (net (code "97") (name "unconnected-(MAX30102-N.C._4-Pad8)") (class "Default")
      (node (ref "MAX30102") (pin "8") (pinfunction "N.C._4_8") (pintype "no_connect"))
    )
    (net (code "98") (name "unconnected-(MAX30102-NC-Pad6)") (class "Default")
      (node (ref "MAX30102") (pin "6") (pinfunction "NC_6") (pintype "passive"))
    )
    (net (code "99") (name "unconnected-(MAX30102-NC_2-Pad5)") (class "Default")
      (node (ref "MAX30102") (pin "5") (pinfunction "NC_2_5") (pintype "passive"))
    )
    (net (code "100") (name "unconnected-(U1-PA0{slash}AD0-Pad78)") (class "Default")
      (node (ref "U1") (pin "78") (pinfunction "PA0/AD0_78") (pintype "bidirectional"))
    )
    (net (code "101") (name "unconnected-(U1-PA1{slash}AD1-Pad77)") (class "Default")
      (node (ref "U1") (pin "77") (pinfunction "PA1/AD1_77") (pintype "bidirectional"))
    )
    (net (code "102") (name "unconnected-(U1-PA2{slash}AD2-Pad76)") (class "Default")
      (node (ref "U1") (pin "76") (pinfunction "PA2/AD2_76") (pintype "bidirectional"))
    )
    (net (code "103") (name "unconnected-(U1-PA3{slash}AD3-Pad75)") (class "Default")
      (node (ref "U1") (pin "75") (pinfunction "PA3/AD3_75") (pintype "bidirectional"))
    )
    (net (code "104") (name "unconnected-(U1-PA4{slash}AD4-Pad74)") (class "Default")
      (node (ref "U1") (pin "74") (pinfunction "PA4/AD4_74") (pintype "bidirectional"))
    )
    (net (code "105") (name "unconnected-(U1-PB5{slash}OC1A{slash}PCINT5-Pad24)") (class "Default")
      (node (ref "U1") (pin "24") (pinfunction "PB5/OC1A/PCINT5_24") (pintype "bidirectional"))
    )
    (net (code "106") (name "unconnected-(U1-PB7{slash}OC0A{slash}OC1C{slash}PCINT7-Pad26)") (class "Default")
      (node (ref "U1") (pin "26") (pinfunction "PB7/OC0A/OC1C/PCINT7_26") (pintype "bidirectional"))
    )
    (net (code "107") (name "unconnected-(U1-PD4{slash}ICP1-Pad47)") (class "Default")
      (node (ref "U1") (pin "47") (pinfunction "PD4/ICP1_47") (pintype "bidirectional"))
    )
    (net (code "108") (name "unconnected-(U1-PD5{slash}XCK1-Pad48)") (class "Default")
      (node (ref "U1") (pin "48") (pinfunction "PD5/XCK1_48") (pintype "bidirectional"))
    )
    (net (code "109") (name "unconnected-(U1-PD6{slash}T1-Pad49)") (class "Default")
      (node (ref "U1") (pin "49") (pinfunction "PD6/T1_49") (pintype "bidirectional"))
    )
    (net (code "110") (name "unconnected-(U1-PE2{slash}XCK0{slash}AIN0-Pad4)") (class "Default")
      (node (ref "U1") (pin "4") (pinfunction "PE2/XCK0/AIN0_4") (pintype "bidirectional"))
    )
    (net (code "111") (name "unconnected-(U1-PE7{slash}CLKO{slash}ICP3{slash}INT7-Pad9)") (class "Default")
      (node (ref "U1") (pin "9") (pinfunction "PE7/CLKO/ICP3/INT7_9") (pintype "bidirectional"))
    )
    (net (code "112") (name "unconnected-(U1-PF2{slash}ADC2-Pad95)") (class "Default")
      (node (ref "U1") (pin "95") (pinfunction "PF2/ADC2_95") (pintype "bidirectional"))
    )
    (net (code "113") (name "unconnected-(U1-PF3{slash}ADC3-Pad94)") (class "Default")
      (node (ref "U1") (pin "94") (pinfunction "PF3/ADC3_94") (pintype "bidirectional"))
    )
    (net (code "114") (name "unconnected-(U1-PG0{slash}~{WR}-Pad51)") (class "Default")
      (node (ref "U1") (pin "51") (pinfunction "PG0/~{WR}_51") (pintype "bidirectional"))
    )
    (net (code "115") (name "unconnected-(U1-PG1{slash}~{RD}-Pad52)") (class "Default")
      (node (ref "U1") (pin "52") (pinfunction "PG1/~{RD}_52") (pintype "bidirectional"))
    )
    (net (code "116") (name "unconnected-(U1-PG2{slash}ALE-Pad70)") (class "Default")
      (node (ref "U1") (pin "70") (pinfunction "PG2/ALE_70") (pintype "bidirectional"))
    )
    (net (code "117") (name "unconnected-(U1-PG3{slash}TOSC2-Pad28)") (class "Default")
      (node (ref "U1") (pin "28") (pinfunction "PG3/TOSC2_28") (pintype "bidirectional"))
    )
    (net (code "118") (name "unconnected-(U1-PG4{slash}TOSC1-Pad29)") (class "Default")
      (node (ref "U1") (pin "29") (pinfunction "PG4/TOSC1_29") (pintype "bidirectional"))
    )
    (net (code "119") (name "unconnected-(U1-PH0{slash}RXD2-Pad12)") (class "Default")
      (node (ref "U1") (pin "12") (pinfunction "PH0/RXD2_12") (pintype "bidirectional"))
    )
    (net (code "120") (name "unconnected-(U1-PH1{slash}TXD2-Pad13)") (class "Default")
      (node (ref "U1") (pin "13") (pinfunction "PH1/TXD2_13") (pintype "bidirectional"))
    )
    (net (code "121") (name "unconnected-(U1-PH7{slash}T4-Pad27)") (class "Default")
      (node (ref "U1") (pin "27") (pinfunction "PH7/T4_27") (pintype "bidirectional"))
    )
    (net (code "122") (name "unconnected-(U1-PJ0{slash}RXD3{slash}PCINT9-Pad63)") (class "Default")
      (node (ref "U1") (pin "63") (pinfunction "PJ0/RXD3/PCINT9_63") (pintype "bidirectional"))
    )
    (net (code "123") (name "unconnected-(U1-PJ1{slash}TXD3{slash}PCINT10-Pad64)") (class "Default")
      (node (ref "U1") (pin "64") (pinfunction "PJ1/TXD3/PCINT10_64") (pintype "bidirectional"))
    )
    (net (code "124") (name "unconnected-(U1-PJ2{slash}XCK3{slash}PCINT11-Pad65)") (class "Default")
      (node (ref "U1") (pin "65") (pinfunction "PJ2/XCK3/PCINT11_65") (pintype "bidirectional"))
    )
    (net (code "125") (name "unconnected-(U1-PJ3{slash}PCINT12-Pad66)") (class "Default")
      (node (ref "U1") (pin "66") (pinfunction "PJ3/PCINT12_66") (pintype "bidirectional"))
    )
    (net (code "126") (name "unconnected-(U1-PJ4{slash}PCINT13-Pad67)") (class "Default")
      (node (ref "U1") (pin "67") (pinfunction "PJ4/PCINT13_67") (pintype "bidirectional"))
    )
    (net (code "127") (name "unconnected-(U1-PJ5{slash}PCINT14-Pad68)") (class "Default")
      (node (ref "U1") (pin "68") (pinfunction "PJ5/PCINT14_68") (pintype "bidirectional"))
    )
    (net (code "128") (name "unconnected-(U1-PJ6{slash}PCINT15-Pad69)") (class "Default")
      (node (ref "U1") (pin "69") (pinfunction "PJ6/PCINT15_69") (pintype "bidirectional"))
    )
    (net (code "129") (name "unconnected-(U1-PJ7-Pad79)") (class "Default")
      (node (ref "U1") (pin "79") (pinfunction "PJ7_79") (pintype "bidirectional"))
    )
    (net (code "130") (name "unconnected-(U1-PK0{slash}ADC8{slash}PCINT16-Pad89)") (class "Default")
      (node (ref "U1") (pin "89") (pinfunction "PK0/ADC8/PCINT16_89") (pintype "bidirectional"))
    )
    (net (code "131") (name "unconnected-(U1-PK1{slash}ADC9{slash}PCINT17-Pad88)") (class "Default")
      (node (ref "U1") (pin "88") (pinfunction "PK1/ADC9/PCINT17_88") (pintype "bidirectional"))
    )
    (net (code "132") (name "unconnected-(U1-PK2{slash}ADC10{slash}PCINT18-Pad87)") (class "Default")
      (node (ref "U1") (pin "87") (pinfunction "PK2/ADC10/PCINT18_87") (pintype "bidirectional"))
    )
    (net (code "133") (name "unconnected-(U1-PK3{slash}ADC11{slash}PCINT19-Pad86)") (class "Default")
      (node (ref "U1") (pin "86") (pinfunction "PK3/ADC11/PCINT19_86") (pintype "bidirectional"))
    )
    (net (code "134") (name "unconnected-(U1-PK4{slash}ADC12{slash}PCINT20-Pad85)") (class "Default")
      (node (ref "U1") (pin "85") (pinfunction "PK4/ADC12/PCINT20_85") (pintype "bidirectional"))
    )
    (net (code "135") (name "unconnected-(U1-PK5{slash}ADC13{slash}PCINT21-Pad84)") (class "Default")
      (node (ref "U1") (pin "84") (pinfunction "PK5/ADC13/PCINT21_84") (pintype "bidirectional"))
    )
    (net (code "136") (name "unconnected-(U1-PK6{slash}ADC14{slash}PCINT22-Pad83)") (class "Default")
      (node (ref "U1") (pin "83") (pinfunction "PK6/ADC14/PCINT22_83") (pintype "bidirectional"))
    )
    (net (code "137") (name "unconnected-(U1-PK7{slash}ADC15{slash}PCINT23-Pad82)") (class "Default")
      (node (ref "U1") (pin "82") (pinfunction "PK7/ADC15/PCINT23_82") (pintype "bidirectional"))
    )
    (net (code "138") (name "unconnected-(U1-PL0{slash}ICP4-Pad35)") (class "Default")
      (node (ref "U1") (pin "35") (pinfunction "PL0/ICP4_35") (pintype "bidirectional"))
    )
    (net (code "139") (name "unconnected-(U1-PL1{slash}ICP5-Pad36)") (class "Default")
      (node (ref "U1") (pin "36") (pinfunction "PL1/ICP5_36") (pintype "bidirectional"))
    )
    (net (code "140") (name "unconnected-(U1-PL2{slash}T5-Pad37)") (class "Default")
      (node (ref "U1") (pin "37") (pinfunction "PL2/T5_37") (pintype "bidirectional"))
    )
    (net (code "141") (name "unconnected-(U1-PL3{slash}OC5A-Pad38)") (class "Default")
      (node (ref "U1") (pin "38") (pinfunction "PL3/OC5A_38") (pintype "bidirectional"))
    )
    (net (code "142") (name "unconnected-(U1-PL4{slash}OC5B-Pad39)") (class "Default")
      (node (ref "U1") (pin "39") (pinfunction "PL4/OC5B_39") (pintype "bidirectional"))
    )
    (net (code "143") (name "unconnected-(U1-PL5{slash}OC5C-Pad40)") (class "Default")
      (node (ref "U1") (pin "40") (pinfunction "PL5/OC5C_40") (pintype "bidirectional"))
    )
    (net (code "144") (name "unconnected-(U1-PL6-Pad41)") (class "Default")
      (node (ref "U1") (pin "41") (pinfunction "PL6_41") (pintype "bidirectional"))
    )
    (net (code "145") (name "unconnected-(U1-PL7-Pad42)") (class "Default")
      (node (ref "U1") (pin "42") (pinfunction "PL7_42") (pintype "bidirectional"))
    )
  )
)
